# 15_-CLOCK.net
KiCad netlist of a schematic drawn in Altium Designer
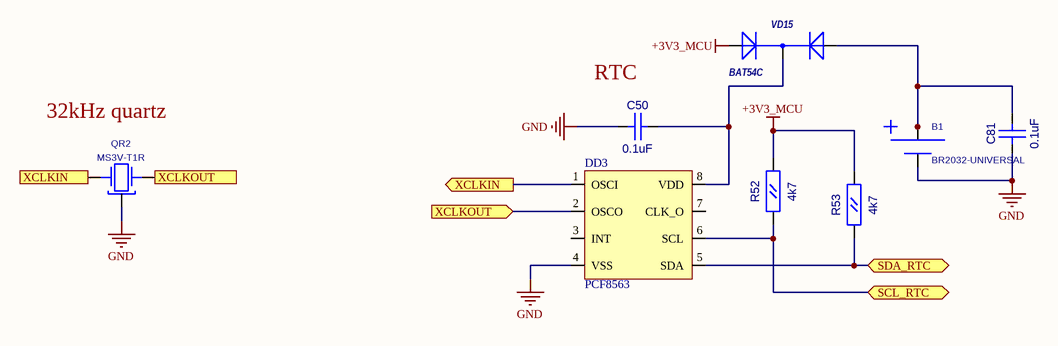
[diagram p0: [15]-CLOCK.SchDoc]

(export (version "E")
  (design (tool "Eeschema 10.0.6"))
  (components
    (comp (ref "B1")
      (value "BR2032-UNIVERSAL")
      (footprint "BR2032-1GU/1HM")
      (libsource (lib "gprs_modem_2") (part "BR2032-UNIVERSAL"))
    )
    (comp (ref "C50")
      (value "0.1uF")
      (footprint "CC0603")
      (description "CC0603")
      (libsource (lib "gprs_modem_2") (part "CC0603"))
    )
    (comp (ref "C81")
      (value "0.1uF")
      (footprint "CC0603")
      (description "CC0603")
      (libsource (lib "fizik_lib") (part "CC0603"))
    )
    (comp (ref "DD3") (value "PCF8563") (footprint "SO-8") (libsource (lib "gprs_modem") (part "PCF8563")))
    (comp (ref "QR2")
      (value "MS3V-T1R")
      (footprint "MS3V-T1R")
      (description "CRYSTAL_32768 Hz")
      (libsource (lib "gprs_modem") (part "MS3V-T1R"))
    )
    (comp (ref "R52")
      (value "4k7")
      (footprint "RC0603")
      (description "RC0603")
      (libsource (lib "gprs_modem_2") (part "RC0603"))
    )
    (comp (ref "R53")
      (value "4k7")
      (footprint "RC0603")
      (description "RC0603")
      (libsource (lib "gprs_modem_2") (part "RC0603"))
    )
    (comp (ref "VD15")
      (value "BAT54C")
      (footprint "SOT-23(123)")
      (libsource (lib "fizik_lib") (part "BAT54C"))
    )
  )
  (nets
    (net (code "1") (name "+3V3_MCU") (class "Default")
      (node (ref "R52") (pin "2") (pinfunction "B_2") (pintype "passive"))
      (node (ref "R53") (pin "2") (pinfunction "B_2") (pintype "passive"))
      (node (ref "VD15") (pin "1") (pinfunction "A_1") (pintype "passive"))
    )
    (net (code "2") (name "/SCL_RTC") (class "Default")
      (node (ref "DD3") (pin "6") (pinfunction "SCL_6") (pintype "passive"))
      (node (ref "R52") (pin "1") (pinfunction "A_1") (pintype "passive"))
    )
    (net (code "3") (name "/SDA_RTC") (class "Default")
      (node (ref "DD3") (pin "5") (pinfunction "SDA_5") (pintype "passive"))
      (node (ref "R53") (pin "1") (pinfunction "A_1") (pintype "passive"))
    )
    (net (code "4") (name "/XCLKIN") (class "Default")
      (node (ref "DD3") (pin "1") (pinfunction "OSCI_1") (pintype "passive"))
      (node (ref "QR2") (pin "2") (pinfunction "X2_2") (pintype "passive"))
    )
    (net (code "5") (name "/XCLKOUT") (class "Default")
      (node (ref "DD3") (pin "2") (pinfunction "OSCO_2") (pintype "passive"))
      (node (ref "QR2") (pin "1") (pinfunction "X1_1") (pintype "passive"))
    )
    (net (code "6") (name "GND") (class "Default")
      (node (ref "B1") (pin "1") (pintype "passive"))
      (node (ref "C50") (pin "1") (pinfunction "A_1") (pintype "passive"))
      (node (ref "C81") (pin "1") (pinfunction "A_1") (pintype "passive"))
      (node (ref "DD3") (pin "4") (pinfunction "VSS_4") (pintype "passive"))
      (node (ref "QR2") (pin "3") (pinfunction "3_3") (pintype "passive"))
    )
    (net (code "7") (name "Net-(C50-B)") (class "Default")
      (node (ref "C50") (pin "2") (pinfunction "B_2") (pintype "passive"))
      (node (ref "DD3") (pin "8") (pinfunction "VDD_8") (pintype "passive"))
      (node (ref "VD15") (pin "3") (pinfunction "K_3") (pintype "passive"))
    )
    (net (code "8") (name "Net-(C81-B)") (class "Default")
      (node (ref "B1") (pin "2") (pintype "passive"))
      (node (ref "B1") (pin "3") (pintype "passive"))
      (node (ref "B1") (pin "4") (pintype "passive"))
      (node (ref "C81") (pin "2") (pinfunction "B_2") (pintype "passive"))
      (node (ref "VD15") (pin "2") (pinfunction "A_2") (pintype "passive"))
    )
    (net (code "9") (name "unconnected-(DD3-CLK_O-Pad7)") (class "Default")
      (node (ref "DD3") (pin "7") (pinfunction "CLK_O_7") (pintype "passive"))
    )
    (net (code "10") (name "unconnected-(DD3-INT-Pad3)") (class "Default")
      (node (ref "DD3") (pin "3") (pinfunction "INT_3") (pintype "passive"))
    )
  )
)
